# project.net
KiCad netlist of a schematic drawn in Altium Designer
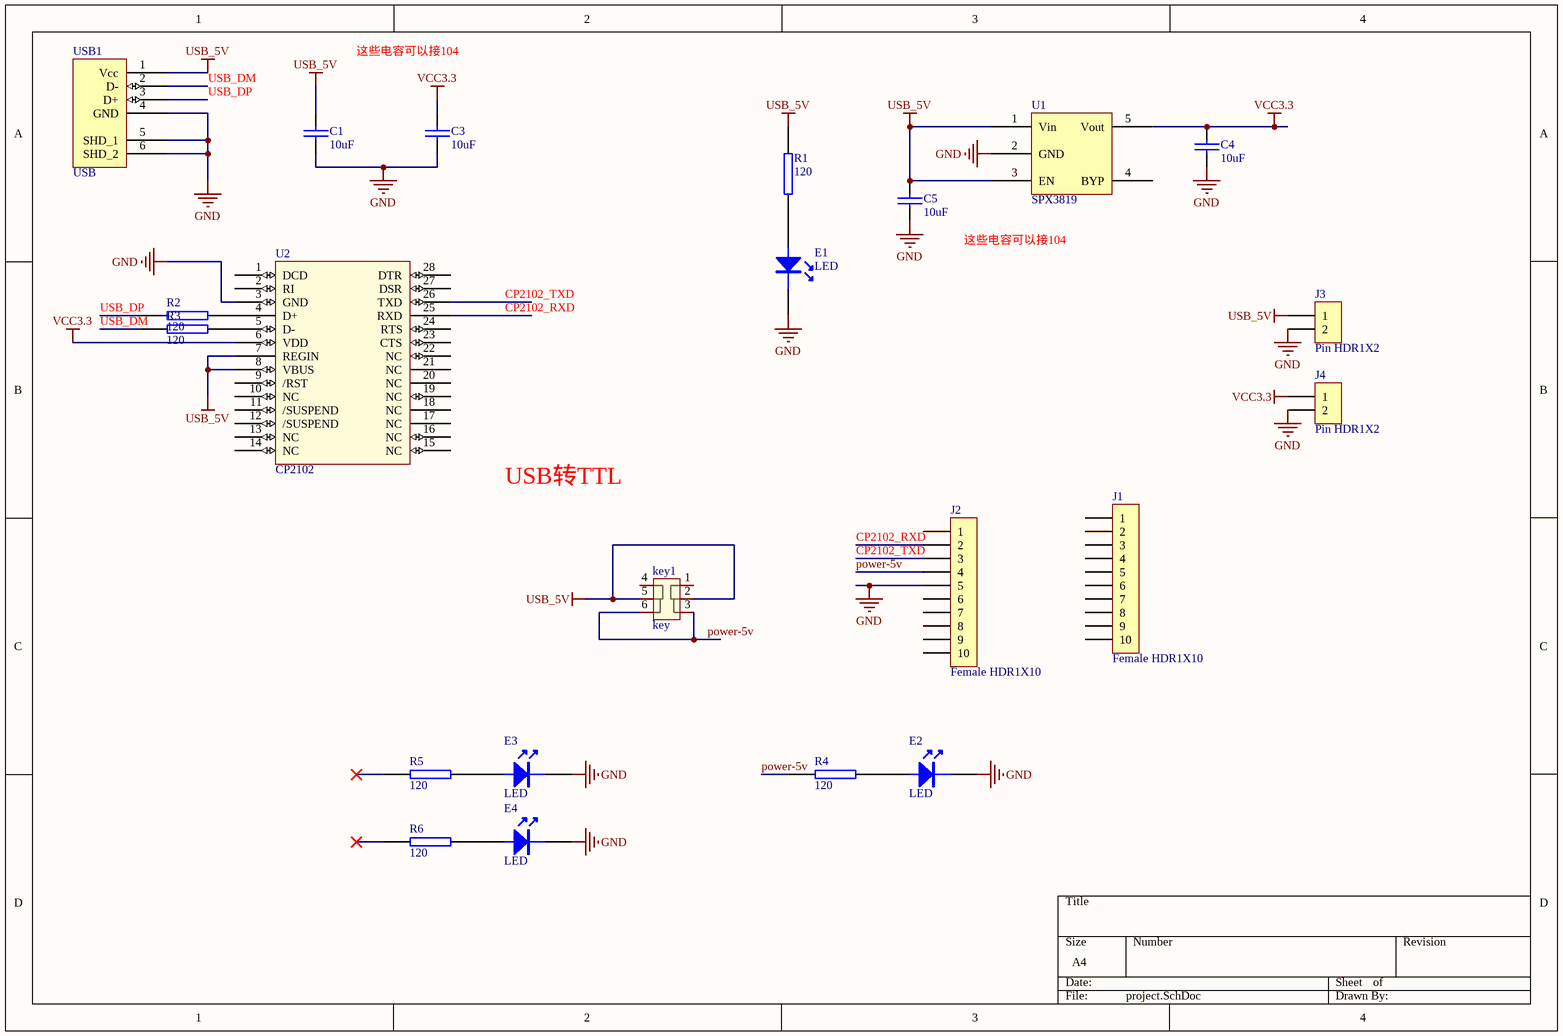
[diagram p0: project.SchDoc]

(export (version "E")
  (design (tool "Eeschema 10.0.6"))
  (components
    (comp (ref "C1")
      (value "10uF")
      (footprint "0603C")
      (description "无极电容")
      (libsource (lib "chenjd") (part "CAP Nonpolarity"))
    )
    (comp (ref "C3")
      (value "10uF")
      (footprint "0603C")
      (description "无极电容")
      (libsource (lib "chenjd") (part "CAP Nonpolarity"))
    )
    (comp (ref "C4")
      (value "10uF")
      (footprint "0603C")
      (description "无极电容")
      (libsource (lib "chenjd") (part "CAP Nonpolarity"))
    )
    (comp (ref "C5")
      (value "10uF")
      (footprint "0603C")
      (description "无极电容")
      (libsource (lib "chenjd") (part "CAP Nonpolarity"))
    )
    (comp (ref "E1")
      (value "LED")
      (footprint "LED_0603L")
      (description "LED灯")
      (libsource (lib "ZXBC") (part "LED"))
    )
    (comp (ref "E2")
      (value "LED")
      (footprint "LED_0603L")
      (description "LED灯")
      (libsource (lib "ZXBC") (part "LED"))
    )
    (comp (ref "E3")
      (value "LED")
      (footprint "LED_0603L")
      (description "LED灯")
      (libsource (lib "ZXBC") (part "LED"))
    )
    (comp (ref "E4")
      (value "LED")
      (footprint "LED_0603L")
      (description "LED灯")
      (libsource (lib "ZXBC") (part "LED"))
    )
    (comp (ref "J1")
      (value "Female HDR1X10")
      (footprint "Fe-HDR1X10/2.54-S")
      (libsource (lib "排母") (part "Female HDR1X10"))
    )
    (comp (ref "J2")
      (value "Female HDR1X10")
      (footprint "Fe-HDR1X10/2.54-S")
      (libsource (lib "排母") (part "Female HDR1X10"))
    )
    (comp (ref "J3")
      (value "Pin HDR1X2")
      (footprint "Pin HDR1X2/2.54mm-S")
      (libsource (lib "排针") (part "Pin HDR1X2"))
    )
    (comp (ref "J4")
      (value "Pin HDR1X2")
      (footprint "Pin HDR1X2/2.54mm-S")
      (libsource (lib "排针") (part "Pin HDR1X2"))
    )
    (comp (ref "key1")
      (value "key")
      (footprint "SW_6P_Lock")
      (description "6pin自锁开关")
      (libsource (lib "chenjd") (part "SW_6pin_Lock"))
    )
    (comp (ref "R1")
      (value "120")
      (footprint "0603R")
      (description "电阻")
      (libsource (lib "chenjd") (part "R"))
    )
    (comp (ref "R2")
      (value "120")
      (footprint "0603R")
      (description "电阻")
      (libsource (lib "chenjd") (part "R"))
    )
    (comp (ref "R3")
      (value "120")
      (footprint "0603R")
      (description "电阻")
      (libsource (lib "chenjd") (part "R"))
    )
    (comp (ref "R4")
      (value "120")
      (footprint "0603R")
      (description "电阻")
      (libsource (lib "chenjd") (part "R"))
    )
    (comp (ref "R5")
      (value "120")
      (footprint "0603R")
      (description "电阻")
      (libsource (lib "chenjd") (part "R"))
    )
    (comp (ref "R6")
      (value "120")
      (footprint "0603R")
      (description "电阻")
      (libsource (lib "chenjd") (part "R"))
    )
    (comp (ref "U1")
      (value "SPX3819")
      (footprint "SOT-23-5")
      (description "稳压器")
      (libsource (lib "ZXBC") (part "SPX3819"))
    )
    (comp (ref "U2")
      (value "CP2102")
      (footprint "QFN28")
      (description "usb转usart")
      (libsource (lib "ZXBC") (part "CP2102"))
    )
    (comp (ref "USB1") (value "USB") (footprint "USB-TB") (libsource (lib "ZXBC") (part "USB")))
  )
  (nets
    (net (code "1") (name "/CP2102_RXD") (class "Default")
      (node (ref "J2") (pin "2") (pinfunction "2_2") (pintype "passive"))
      (node (ref "U2") (pin "25") (pinfunction "RXD_25") (pintype "power_in"))
    )
    (net (code "2") (name "/CP2102_TXD") (class "Default")
      (node (ref "J2") (pin "3") (pinfunction "3_3") (pintype "passive"))
      (node (ref "U2") (pin "26") (pinfunction "TXD_26") (pintype "bidirectional"))
    )
    (net (code "3") (name "/USB_DM") (class "Default")
      (node (ref "R3") (pin "1") (pinfunction "1_1") (pintype "passive"))
      (node (ref "USB1") (pin "2") (pinfunction "D-_2") (pintype "bidirectional"))
    )
    (net (code "4") (name "/USB_DP") (class "Default")
      (node (ref "R2") (pin "1") (pinfunction "1_1") (pintype "passive"))
      (node (ref "USB1") (pin "3") (pinfunction "D+_3") (pintype "bidirectional"))
    )
    (net (code "5") (name "/power-5v") (class "Default")
      (node (ref "J2") (pin "4") (pinfunction "4_4") (pintype "passive"))
      (node (ref "R4") (pin "2") (pinfunction "2_2") (pintype "passive"))
      (node (ref "key1") (pin "3") (pinfunction "3_3") (pintype "passive"))
      (node (ref "key1") (pin "6") (pinfunction "6_6") (pintype "passive"))
    )
    (net (code "6") (name "GND") (class "Default")
      (node (ref "C1") (pin "2") (pinfunction "2_2") (pintype "passive"))
      (node (ref "C3") (pin "2") (pinfunction "2_2") (pintype "passive"))
      (node (ref "C4") (pin "2") (pinfunction "2_2") (pintype "passive"))
      (node (ref "C5") (pin "2") (pinfunction "2_2") (pintype "passive"))
      (node (ref "E1") (pin "2") (pinfunction "2_2") (pintype "passive"))
      (node (ref "E2") (pin "2") (pinfunction "2_2") (pintype "passive"))
      (node (ref "E3") (pin "2") (pinfunction "2_2") (pintype "passive"))
      (node (ref "E4") (pin "2") (pinfunction "2_2") (pintype "passive"))
      (node (ref "J2") (pin "5") (pinfunction "5_5") (pintype "passive"))
      (node (ref "J3") (pin "2") (pinfunction "2_2") (pintype "passive"))
      (node (ref "J4") (pin "2") (pinfunction "2_2") (pintype "passive"))
      (node (ref "U1") (pin "2") (pinfunction "GND_2") (pintype "passive"))
      (node (ref "U2") (pin "3") (pinfunction "GND_3") (pintype "bidirectional"))
      (node (ref "USB1") (pin "4") (pinfunction "GND_4") (pintype "passive"))
      (node (ref "USB1") (pin "5") (pinfunction "SHD_1_5") (pintype "passive"))
      (node (ref "USB1") (pin "6") (pinfunction "SHD_2_6") (pintype "passive"))
    )
    (net (code "7") (name "Net-(E1-Pad1)") (class "Default")
      (node (ref "E1") (pin "1") (pinfunction "1_1") (pintype "passive"))
      (node (ref "R1") (pin "1") (pinfunction "1_1") (pintype "passive"))
    )
    (net (code "8") (name "Net-(E2-Pad1)") (class "Default")
      (node (ref "E2") (pin "1") (pinfunction "1_1") (pintype "passive"))
      (node (ref "R4") (pin "1") (pinfunction "1_1") (pintype "passive"))
    )
    (net (code "9") (name "Net-(E3-Pad1)") (class "Default")
      (node (ref "E3") (pin "1") (pinfunction "1_1") (pintype "passive"))
      (node (ref "R5") (pin "1") (pinfunction "1_1") (pintype "passive"))
    )
    (net (code "10") (name "Net-(E4-Pad1)") (class "Default")
      (node (ref "E4") (pin "1") (pinfunction "1_1") (pintype "passive"))
      (node (ref "R6") (pin "1") (pinfunction "1_1") (pintype "passive"))
    )
    (net (code "11") (name "Net-(U2-D+)") (class "Default")
      (node (ref "R2") (pin "2") (pinfunction "2_2") (pintype "passive"))
      (node (ref "U2") (pin "4") (pinfunction "D+_4") (pintype "power_in"))
    )
    (net (code "12") (name "Net-(U2-D-)") (class "Default")
      (node (ref "R3") (pin "2") (pinfunction "2_2") (pintype "passive"))
      (node (ref "U2") (pin "5") (pinfunction "D-_5") (pintype "bidirectional"))
    )
    (net (code "13") (name "USB_5V") (class "Default")
      (node (ref "C1") (pin "1") (pinfunction "1_1") (pintype "passive"))
      (node (ref "C5") (pin "1") (pinfunction "1_1") (pintype "passive"))
      (node (ref "J3") (pin "1") (pinfunction "1_1") (pintype "passive"))
      (node (ref "R1") (pin "2") (pinfunction "2_2") (pintype "passive"))
      (node (ref "U1") (pin "1") (pinfunction "Vin_1") (pintype "passive"))
      (node (ref "U1") (pin "3") (pinfunction "EN_3") (pintype "passive"))
      (node (ref "U2") (pin "7") (pinfunction "REGIN_7") (pintype "power_in"))
      (node (ref "U2") (pin "8") (pinfunction "VBUS_8") (pintype "bidirectional"))
      (node (ref "USB1") (pin "1") (pinfunction "Vcc_1") (pintype "passive"))
      (node (ref "key1") (pin "2") (pinfunction "2_2") (pintype "passive"))
      (node (ref "key1") (pin "5") (pinfunction "5_5") (pintype "passive"))
    )
    (net (code "14") (name "VCC3.3") (class "Default")
      (node (ref "C3") (pin "1") (pinfunction "1_1") (pintype "passive"))
      (node (ref "C4") (pin "1") (pinfunction "1_1") (pintype "passive"))
      (node (ref "J4") (pin "1") (pinfunction "1_1") (pintype "passive"))
      (node (ref "U1") (pin "5") (pinfunction "Vout_5") (pintype "passive"))
      (node (ref "U2") (pin "6") (pinfunction "VDD_6") (pintype "bidirectional"))
    )
    (net (code "15") (name "unconnected-(J1-Pad1)") (class "Default")
      (node (ref "J1") (pin "1") (pinfunction "1_1") (pintype "passive"))
    )
    (net (code "16") (name "unconnected-(J1-Pad2)") (class "Default")
      (node (ref "J1") (pin "2") (pinfunction "2_2") (pintype "passive"))
    )
    (net (code "17") (name "unconnected-(J1-Pad3)") (class "Default")
      (node (ref "J1") (pin "3") (pinfunction "3_3") (pintype "passive"))
    )
    (net (code "18") (name "unconnected-(J1-Pad4)") (class "Default")
      (node (ref "J1") (pin "4") (pinfunction "4_4") (pintype "passive"))
    )
    (net (code "19") (name "unconnected-(J1-Pad5)") (class "Default")
      (node (ref "J1") (pin "5") (pinfunction "5_5") (pintype "passive"))
    )
    (net (code "20") (name "unconnected-(J1-Pad6)") (class "Default")
      (node (ref "J1") (pin "6") (pinfunction "6_6") (pintype "passive"))
    )
    (net (code "21") (name "unconnected-(J1-Pad7)") (class "Default")
      (node (ref "J1") (pin "7") (pinfunction "7_7") (pintype "passive"))
    )
    (net (code "22") (name "unconnected-(J1-Pad8)") (class "Default")
      (node (ref "J1") (pin "8") (pinfunction "8_8") (pintype "passive"))
    )
    (net (code "23") (name "unconnected-(J1-Pad9)") (class "Default")
      (node (ref "J1") (pin "9") (pinfunction "9_9") (pintype "passive"))
    )
    (net (code "24") (name "unconnected-(J1-Pad10)") (class "Default")
      (node (ref "J1") (pin "10") (pinfunction "10_10") (pintype "passive"))
    )
    (net (code "25") (name "unconnected-(J2-Pad1)") (class "Default")
      (node (ref "J2") (pin "1") (pinfunction "1_1") (pintype "passive"))
    )
    (net (code "26") (name "unconnected-(J2-Pad6)") (class "Default")
      (node (ref "J2") (pin "6") (pinfunction "6_6") (pintype "passive"))
    )
    (net (code "27") (name "unconnected-(J2-Pad7)") (class "Default")
      (node (ref "J2") (pin "7") (pinfunction "7_7") (pintype "passive"))
    )
    (net (code "28") (name "unconnected-(J2-Pad8)") (class "Default")
      (node (ref "J2") (pin "8") (pinfunction "8_8") (pintype "passive"))
    )
    (net (code "29") (name "unconnected-(J2-Pad9)") (class "Default")
      (node (ref "J2") (pin "9") (pinfunction "9_9") (pintype "passive"))
    )
    (net (code "30") (name "unconnected-(J2-Pad10)") (class "Default")
      (node (ref "J2") (pin "10") (pinfunction "10_10") (pintype "passive"))
    )
    (net (code "31") (name "unconnected-(R5-Pad2)") (class "Default")
      (node (ref "R5") (pin "2") (pinfunction "2_2") (pintype "passive+no_connect"))
    )
    (net (code "32") (name "unconnected-(R6-Pad2)") (class "Default")
      (node (ref "R6") (pin "2") (pinfunction "2_2") (pintype "passive+no_connect"))
    )
    (net (code "33") (name "unconnected-(U1-BYP-Pad4)") (class "Default")
      (node (ref "U1") (pin "4") (pinfunction "BYP_4") (pintype "passive"))
    )
    (net (code "34") (name "unconnected-(U2-CTS-Pad23)") (class "Default")
      (node (ref "U2") (pin "23") (pinfunction "CTS_23") (pintype "bidirectional"))
    )
    (net (code "35") (name "unconnected-(U2-DCD-Pad1)") (class "Default")
      (node (ref "U2") (pin "1") (pinfunction "DCD_1") (pintype "bidirectional"))
    )
    (net (code "36") (name "unconnected-(U2-DSR-Pad27)") (class "Default")
      (node (ref "U2") (pin "27") (pinfunction "DSR_27") (pintype "bidirectional"))
    )
    (net (code "37") (name "unconnected-(U2-DTR-Pad28)") (class "Default")
      (node (ref "U2") (pin "28") (pinfunction "DTR_28") (pintype "bidirectional"))
    )
    (net (code "38") (name "unconnected-(U2-NC-Pad10)") (class "Default")
      (node (ref "U2") (pin "10") (pinfunction "NC_10") (pintype "bidirectional"))
    )
    (net (code "39") (name "unconnected-(U2-NC-Pad13)") (class "Default")
      (node (ref "U2") (pin "13") (pinfunction "NC_13") (pintype "bidirectional"))
    )
    (net (code "40") (name "unconnected-(U2-NC-Pad14)") (class "Default")
      (node (ref "U2") (pin "14") (pinfunction "NC_14") (pintype "bidirectional"))
    )
    (net (code "41") (name "unconnected-(U2-NC-Pad15)") (class "Default")
      (node (ref "U2") (pin "15") (pinfunction "NC_15") (pintype "bidirectional"))
    )
    (net (code "42") (name "unconnected-(U2-NC-Pad16)") (class "Default")
      (node (ref "U2") (pin "16") (pinfunction "NC_16") (pintype "bidirectional"))
    )
    (net (code "43") (name "unconnected-(U2-NC-Pad17)") (class "Default")
      (node (ref "U2") (pin "17") (pinfunction "NC_17") (pintype "power_in"))
    )
    (net (code "44") (name "unconnected-(U2-NC-Pad18)") (class "Default")
      (node (ref "U2") (pin "18") (pinfunction "NC_18") (pintype "power_in"))
    )
    (net (code "45") (name "unconnected-(U2-NC-Pad19)") (class "Default")
      (node (ref "U2") (pin "19") (pinfunction "NC_19") (pintype "bidirectional"))
    )
    (net (code "46") (name "unconnected-(U2-NC-Pad20)") (class "Default")
      (node (ref "U2") (pin "20") (pinfunction "NC_20") (pintype "power_in"))
    )
    (net (code "47") (name "unconnected-(U2-NC-Pad21)") (class "Default")
      (node (ref "U2") (pin "21") (pinfunction "NC_21") (pintype "power_in"))
    )
    (net (code "48") (name "unconnected-(U2-NC-Pad22)") (class "Default")
      (node (ref "U2") (pin "22") (pinfunction "NC_22") (pintype "bidirectional"))
    )
    (net (code "49") (name "unconnected-(U2-RI-Pad2)") (class "Default")
      (node (ref "U2") (pin "2") (pinfunction "RI_2") (pintype "bidirectional"))
    )
    (net (code "50") (name "unconnected-(U2-RTS-Pad24)") (class "Default")
      (node (ref "U2") (pin "24") (pinfunction "RTS_24") (pintype "bidirectional"))
    )
    (net (code "51") (name "unconnected-(U2-{slash}RST-Pad9)") (class "Default")
      (node (ref "U2") (pin "9") (pinfunction "/RST_9") (pintype "bidirectional"))
    )
    (net (code "52") (name "unconnected-(U2-{slash}SUSPEND-Pad11)") (class "Default")
      (node (ref "U2") (pin "11") (pinfunction "/SUSPEND_11") (pintype "bidirectional"))
    )
    (net (code "53") (name "unconnected-(U2-{slash}SUSPEND-Pad12)") (class "Default")
      (node (ref "U2") (pin "12") (pinfunction "/SUSPEND_12") (pintype "bidirectional"))
    )
    (net (code "54") (name "unconnected-(key1-Pad1)") (class "Default")
      (node (ref "key1") (pin "1") (pinfunction "1_1") (pintype "passive"))
    )
    (net (code "55") (name "unconnected-(key1-Pad4)") (class "Default")
      (node (ref "key1") (pin "4") (pinfunction "4_4") (pintype "passive"))
    )
  )
)
